# monoamp.net
KiCad netlist of a schematic drawn in EAGLE
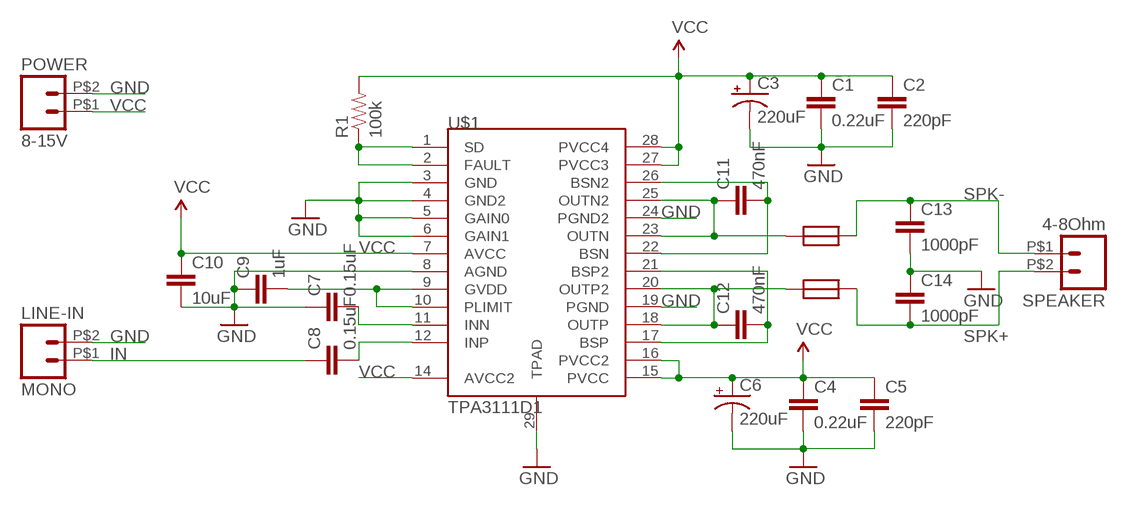
[diagram p0: schematic, sheet 1]

(export (version "E")
  (design (tool "Eeschema 10.0.6"))
  (components
    (comp (ref "C1")
      (value "0.22uF")
      (footprint "eagle-import:0603-CAP")
      (libsource (lib "eagle-import") (part "CAP0603-CAP"))
    )
    (comp (ref "C2")
      (value "220pF")
      (footprint "eagle-import:0603-CAP")
      (libsource (lib "eagle-import") (part "CAP0603-CAP"))
    )
    (comp (ref "C3")
      (value "220uF")
      (footprint "eagle-import:NICHICON_10")
      (libsource (lib "eagle-import") (part "CAP_POLNICHICON-10"))
    )
    (comp (ref "C4")
      (value "0.22uF")
      (footprint "eagle-import:0603-CAP")
      (libsource (lib "eagle-import") (part "CAP0603-CAP"))
    )
    (comp (ref "C5")
      (value "220pF")
      (footprint "eagle-import:0603-CAP")
      (libsource (lib "eagle-import") (part "CAP0603-CAP"))
    )
    (comp (ref "C6")
      (value "220uF")
      (footprint "eagle-import:NICHICON_10")
      (libsource (lib "eagle-import") (part "CAP_POLNICHICON-10"))
    )
    (comp (ref "C7")
      (value "0.15uF")
      (footprint "eagle-import:0603-CAP")
      (libsource (lib "eagle-import") (part "CAP0603-CAP"))
    )
    (comp (ref "C8")
      (value "0.15uF")
      (footprint "eagle-import:0603-CAP")
      (libsource (lib "eagle-import") (part "CAP0603-CAP"))
    )
    (comp (ref "C9")
      (value "1uF")
      (footprint "eagle-import:0603-CAP")
      (libsource (lib "eagle-import") (part "CAP0603-CAP"))
    )
    (comp (ref "C10")
      (value "10uF")
      (footprint "eagle-import:0805")
      (libsource (lib "eagle-import") (part "CAP0805"))
    )
    (comp (ref "C11")
      (value "470nF")
      (footprint "eagle-import:0603-CAP")
      (libsource (lib "eagle-import") (part "CAP0603-CAP"))
    )
    (comp (ref "C12")
      (value "470nF")
      (footprint "eagle-import:0603-CAP")
      (libsource (lib "eagle-import") (part "CAP0603-CAP"))
    )
    (comp (ref "C13")
      (value "1000pF")
      (footprint "eagle-import:0603-CAP")
      (libsource (lib "eagle-import") (part "CAP0603-CAP"))
    )
    (comp (ref "C14")
      (value "1000pF")
      (footprint "eagle-import:0603-CAP")
      (libsource (lib "eagle-import") (part "CAP0603-CAP"))
    )
    (comp (ref "LINE-IN")
      (value "MONO")
      (footprint "eagle-import:1X02_BIG")
      (libsource (lib "eagle-import") (part "M02PTH2"))
    )
    (comp (ref "POWER")
      (value "8-15V")
      (footprint "eagle-import:1X02_BIG")
      (libsource (lib "eagle-import") (part "M02PTH2"))
    )
    (comp (ref "R1")
      (value "100k")
      (footprint "eagle-import:0603-RES")
      (libsource (lib "eagle-import") (part "RESISTOR0603-RES"))
    )
    (comp (ref "SPEAKER")
      (value "4-8Ohm")
      (footprint "eagle-import:1X02_BIG")
      (libsource (lib "eagle-import") (part "M02PTH2"))
    )
    (comp (ref "U$1")
      (value "TPA3111D1")
      (footprint "eagle-import:TSSOP28-GROUNDPAD")
      (libsource (lib "eagle-import") (part "TPA3111D1"))
    )
    (comp (ref "U$2")
      (value "FERRITE-BEAD28L0138-80R-10")
      (footprint "eagle-import:0138")
      (libsource (lib "eagle-import") (part "FERRITE-BEAD28L0138-80R-10"))
    )
    (comp (ref "U$3")
      (value "FERRITE-BEAD28L0138-80R-10")
      (footprint "eagle-import:0138")
      (libsource (lib "eagle-import") (part "FERRITE-BEAD28L0138-80R-10"))
    )
  )
  (nets
    (net (code "1") (name "/IN") (class "Default")
      (node (ref "C8") (pin "1") (pinfunction "1_1") (pintype "passive"))
      (node (ref "LINE-IN") (pin "P$1") (pinfunction "1_P$1") (pintype "passive"))
    )
    (net (code "2") (name "/SPK+") (class "Default")
      (node (ref "C14") (pin "2") (pinfunction "2_2") (pintype "passive"))
      (node (ref "SPEAKER") (pin "P$2") (pinfunction "2_P$2") (pintype "passive"))
      (node (ref "U$3") (pin "P$2") (pinfunction "P$2_P$2") (pintype "bidirectional"))
    )
    (net (code "3") (name "/SPK-") (class "Default")
      (node (ref "C13") (pin "1") (pinfunction "1_1") (pintype "passive"))
      (node (ref "SPEAKER") (pin "P$1") (pinfunction "1_P$1") (pintype "passive"))
      (node (ref "U$2") (pin "P$2") (pinfunction "P$2_P$2") (pintype "bidirectional"))
    )
    (net (code "4") (name "GND") (class "Default")
      (node (ref "C1") (pin "2") (pinfunction "2_2") (pintype "passive"))
      (node (ref "C10") (pin "2") (pinfunction "2_2") (pintype "passive"))
      (node (ref "C13") (pin "2") (pinfunction "2_2") (pintype "passive"))
      (node (ref "C14") (pin "1") (pinfunction "1_1") (pintype "passive"))
      (node (ref "C2") (pin "2") (pinfunction "2_2") (pintype "passive"))
      (node (ref "C3") (pin "-") (pinfunction "-_-") (pintype "passive"))
      (node (ref "C4") (pin "2") (pinfunction "2_2") (pintype "passive"))
      (node (ref "C5") (pin "2") (pinfunction "2_2") (pintype "passive"))
      (node (ref "C6") (pin "-") (pinfunction "-_-") (pintype "passive"))
      (node (ref "C7") (pin "1") (pinfunction "1_1") (pintype "passive"))
      (node (ref "C9") (pin "1") (pinfunction "1_1") (pintype "passive"))
      (node (ref "LINE-IN") (pin "P$2") (pinfunction "2_P$2") (pintype "passive"))
      (node (ref "POWER") (pin "P$2") (pinfunction "2_P$2") (pintype "passive"))
      (node (ref "U$1") (pin "19") (pinfunction "PGND_19") (pintype "bidirectional"))
      (node (ref "U$1") (pin "24") (pinfunction "PGND2_24") (pintype "bidirectional"))
      (node (ref "U$1") (pin "29") (pinfunction "TPAD_29") (pintype "bidirectional"))
      (node (ref "U$1") (pin "3") (pinfunction "GND_3") (pintype "bidirectional"))
      (node (ref "U$1") (pin "4") (pinfunction "GND2_4") (pintype "bidirectional"))
      (node (ref "U$1") (pin "5") (pinfunction "GAIN0_5") (pintype "bidirectional"))
      (node (ref "U$1") (pin "6") (pinfunction "GAIN1_6") (pintype "bidirectional"))
      (node (ref "U$1") (pin "8") (pinfunction "AGND_8") (pintype "input"))
    )
    (net (code "5") (name "Net-(U$1-BSN)") (class "Default")
      (node (ref "C11") (pin "2") (pinfunction "2_2") (pintype "passive"))
      (node (ref "U$1") (pin "22") (pinfunction "BSN_22") (pintype "bidirectional"))
      (node (ref "U$1") (pin "26") (pinfunction "BSN2_26") (pintype "bidirectional"))
    )
    (net (code "6") (name "Net-(U$1-BSP)") (class "Default")
      (node (ref "C12") (pin "2") (pinfunction "2_2") (pintype "passive"))
      (node (ref "U$1") (pin "17") (pinfunction "BSP_17") (pintype "bidirectional"))
      (node (ref "U$1") (pin "21") (pinfunction "BSP2_21") (pintype "bidirectional"))
    )
    (net (code "7") (name "Net-(U$1-FAULT)") (class "Default")
      (node (ref "R1") (pin "1") (pinfunction "1_1") (pintype "passive"))
      (node (ref "U$1") (pin "1") (pinfunction "SD_1") (pintype "input"))
      (node (ref "U$1") (pin "2") (pinfunction "FAULT_2") (pintype "output"))
    )
    (net (code "8") (name "Net-(U$1-GVDD)") (class "Default")
      (node (ref "C9") (pin "2") (pinfunction "2_2") (pintype "passive"))
      (node (ref "U$1") (pin "10") (pinfunction "PLIMIT_10") (pintype "bidirectional"))
      (node (ref "U$1") (pin "9") (pinfunction "GVDD_9") (pintype "power_in"))
    )
    (net (code "9") (name "Net-(U$1-INN)") (class "Default")
      (node (ref "C7") (pin "2") (pinfunction "2_2") (pintype "passive"))
      (node (ref "U$1") (pin "11") (pinfunction "INN_11") (pintype "bidirectional"))
    )
    (net (code "10") (name "Net-(U$1-INP)") (class "Default")
      (node (ref "C8") (pin "2") (pinfunction "2_2") (pintype "passive"))
      (node (ref "U$1") (pin "12") (pinfunction "INP_12") (pintype "bidirectional"))
    )
    (net (code "11") (name "Net-(U$1-OUTN)") (class "Default")
      (node (ref "C11") (pin "1") (pinfunction "1_1") (pintype "passive"))
      (node (ref "U$1") (pin "23") (pinfunction "OUTN_23") (pintype "output"))
      (node (ref "U$1") (pin "25") (pinfunction "OUTN2_25") (pintype "output"))
      (node (ref "U$2") (pin "P$1") (pinfunction "P$1_P$1") (pintype "bidirectional"))
    )
    (net (code "12") (name "Net-(U$1-OUTP)") (class "Default")
      (node (ref "C12") (pin "1") (pinfunction "1_1") (pintype "passive"))
      (node (ref "U$1") (pin "18") (pinfunction "OUTP_18") (pintype "output"))
      (node (ref "U$1") (pin "20") (pinfunction "OUTP2_20") (pintype "output"))
      (node (ref "U$3") (pin "P$1") (pinfunction "P$1_P$1") (pintype "bidirectional"))
    )
    (net (code "13") (name "VCC") (class "Default")
      (node (ref "C1") (pin "1") (pinfunction "1_1") (pintype "passive"))
      (node (ref "C10") (pin "1") (pinfunction "1_1") (pintype "passive"))
      (node (ref "C2") (pin "1") (pinfunction "1_1") (pintype "passive"))
      (node (ref "C3") (pin "+") (pinfunction "+_+") (pintype "passive"))
      (node (ref "C4") (pin "1") (pinfunction "1_1") (pintype "passive"))
      (node (ref "C5") (pin "1") (pinfunction "1_1") (pintype "passive"))
      (node (ref "C6") (pin "+") (pinfunction "+_+") (pintype "passive"))
      (node (ref "POWER") (pin "P$1") (pinfunction "1_P$1") (pintype "passive"))
      (node (ref "R1") (pin "2") (pinfunction "2_2") (pintype "passive"))
      (node (ref "U$1") (pin "14") (pinfunction "AVCC2_14") (pintype "power_in"))
      (node (ref "U$1") (pin "15") (pinfunction "PVCC_15") (pintype "power_in"))
      (node (ref "U$1") (pin "16") (pinfunction "PVCC2_16") (pintype "power_in"))
      (node (ref "U$1") (pin "27") (pinfunction "PVCC3_27") (pintype "power_in"))
      (node (ref "U$1") (pin "28") (pinfunction "PVCC4_28") (pintype "power_in"))
      (node (ref "U$1") (pin "7") (pinfunction "AVCC_7") (pintype "power_in"))
    )
  )
)
